# Robot_Psoc.net
KiCad netlist of a schematic drawn in EAGLE
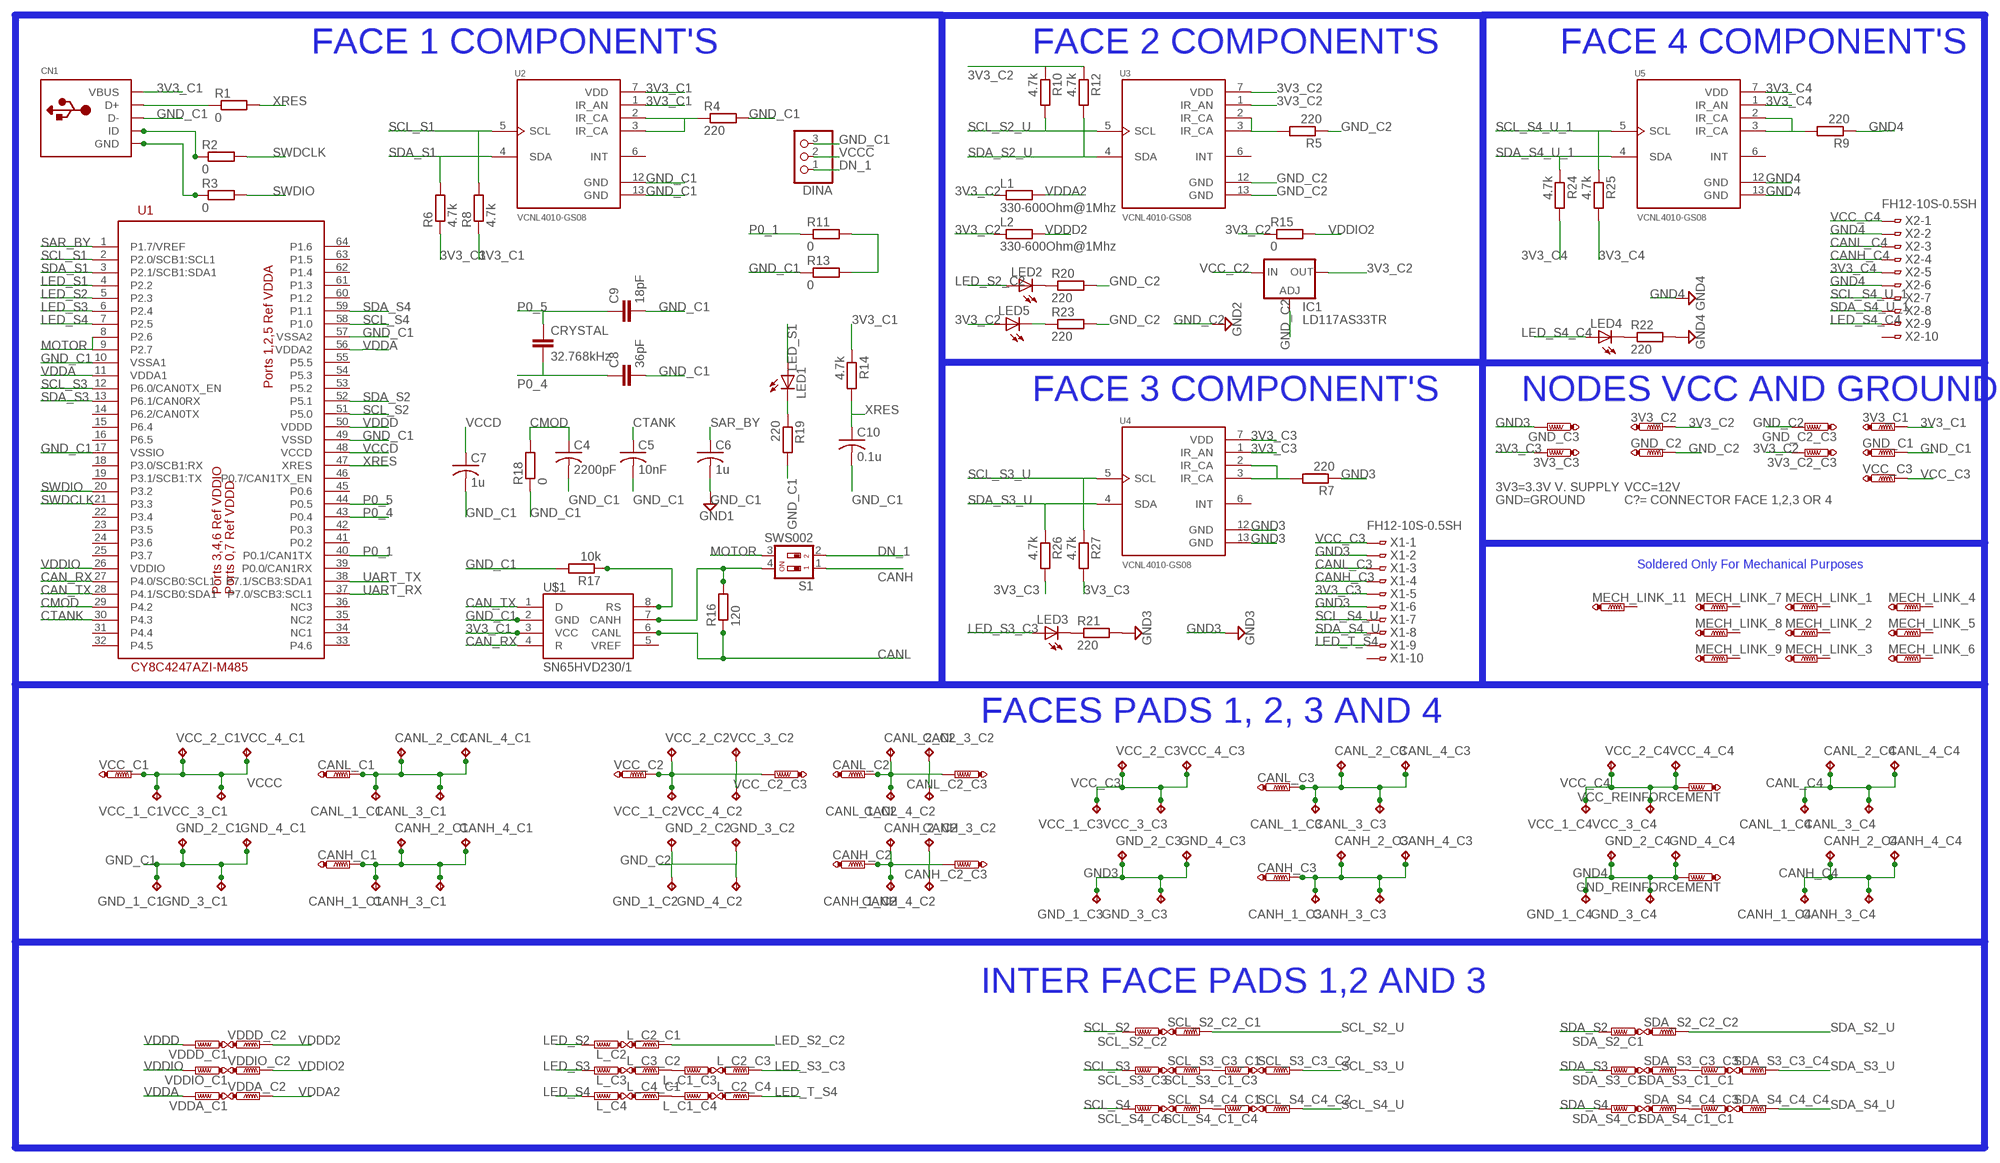
[diagram p0: schematic, sheet 1]

(export (version "E")
  (design (tool "Eeschema 10.0.6"))
  (components
    (comp (ref "3V3_C1")
      (value "PTR1TP11R")
      (footprint "eagle-import:TP11R")
      (libsource (lib "eagle-import") (part "PTR1TP11R"))
    )
    (comp (ref "3V3_C2")
      (value "PTR1TP11R")
      (footprint "eagle-import:TP11R")
      (libsource (lib "eagle-import") (part "PTR1TP11R"))
    )
    (comp (ref "3V3_C2_C3")
      (value "PTR1TP11R")
      (footprint "eagle-import:TP11R")
      (libsource (lib "eagle-import") (part "PTR1TP11R"))
    )
    (comp (ref "3V3_C3")
      (value "PTR1TP11R")
      (footprint "eagle-import:TP11R")
      (libsource (lib "eagle-import") (part "PTR1TP11R"))
    )
    (comp (ref "C4")
      (value "2200pF")
      (footprint "eagle-import:C0805")
      (libsource (lib "eagle-import") (part "C-USC0805"))
    )
    (comp (ref "C5")
      (value "10nF")
      (footprint "eagle-import:C0805")
      (libsource (lib "eagle-import") (part "C-USC0805"))
    )
    (comp (ref "C6")
      (value "1u")
      (footprint "eagle-import:C0805")
      (libsource (lib "eagle-import") (part "C-USC0805"))
    )
    (comp (ref "C7")
      (value "1u")
      (footprint "eagle-import:C0805")
      (libsource (lib "eagle-import") (part "C-USC0805"))
    )
    (comp (ref "C8")
      (value "36pF")
      (footprint "eagle-import:C0805")
      (libsource (lib "eagle-import") (part "C-EUC0805"))
    )
    (comp (ref "C9")
      (value "18pF")
      (footprint "eagle-import:C0805")
      (libsource (lib "eagle-import") (part "C-EUC0805"))
    )
    (comp (ref "C10")
      (value "0.1u")
      (footprint "eagle-import:C0805")
      (libsource (lib "eagle-import") (part "C-USC0805"))
    )
    (comp (ref "CANH_1_C1")
      (value "TPB2,54")
      (footprint "eagle-import:B2,54")
      (libsource (lib "eagle-import") (part "TPB2,54"))
    )
    (comp (ref "CANH_1_C2")
      (value "TPB2,54")
      (footprint "eagle-import:B2,54")
      (libsource (lib "eagle-import") (part "TPB2,54"))
    )
    (comp (ref "CANH_1_C3")
      (value "TPB2,54")
      (footprint "eagle-import:B2,54")
      (libsource (lib "eagle-import") (part "TPB2,54"))
    )
    (comp (ref "CANH_1_C4")
      (value "TPB2,54")
      (footprint "eagle-import:B2,54")
      (libsource (lib "eagle-import") (part "TPB2,54"))
    )
    (comp (ref "CANH_2_C1")
      (value "TPB2,54")
      (footprint "eagle-import:B2,54")
      (libsource (lib "eagle-import") (part "TPB2,54"))
    )
    (comp (ref "CANH_2_C2")
      (value "TPB2,54")
      (footprint "eagle-import:B2,54")
      (libsource (lib "eagle-import") (part "TPB2,54"))
    )
    (comp (ref "CANH_2_C3")
      (value "TPB2,54")
      (footprint "eagle-import:B2,54")
      (libsource (lib "eagle-import") (part "TPB2,54"))
    )
    (comp (ref "CANH_2_C4")
      (value "TPB2,54")
      (footprint "eagle-import:B2,54")
      (libsource (lib "eagle-import") (part "TPB2,54"))
    )
    (comp (ref "CANH_3_C1")
      (value "TPB2,54")
      (footprint "eagle-import:B2,54")
      (libsource (lib "eagle-import") (part "TPB2,54"))
    )
    (comp (ref "CANH_3_C2")
      (value "TPB2,54")
      (footprint "eagle-import:B2,54")
      (libsource (lib "eagle-import") (part "TPB2,54"))
    )
    (comp (ref "CANH_3_C3")
      (value "TPB2,54")
      (footprint "eagle-import:B2,54")
      (libsource (lib "eagle-import") (part "TPB2,54"))
    )
    (comp (ref "CANH_3_C4")
      (value "TPB2,54")
      (footprint "eagle-import:B2,54")
      (libsource (lib "eagle-import") (part "TPB2,54"))
    )
    (comp (ref "CANH_4_C1")
      (value "TPB2,54")
      (footprint "eagle-import:B2,54")
      (libsource (lib "eagle-import") (part "TPB2,54"))
    )
    (comp (ref "CANH_4_C2")
      (value "TPB2,54")
      (footprint "eagle-import:B2,54")
      (libsource (lib "eagle-import") (part "TPB2,54"))
    )
    (comp (ref "CANH_4_C3")
      (value "TPB2,54")
      (footprint "eagle-import:B2,54")
      (libsource (lib "eagle-import") (part "TPB2,54"))
    )
    (comp (ref "CANH_4_C4")
      (value "TPB2,54")
      (footprint "eagle-import:B2,54")
      (libsource (lib "eagle-import") (part "TPB2,54"))
    )
    (comp (ref "CANH_C1")
      (value "PTR1TP11R")
      (footprint "eagle-import:TP11R")
      (libsource (lib "eagle-import") (part "PTR1TP11R"))
    )
    (comp (ref "CANH_C2")
      (value "PTR1TP11R")
      (footprint "eagle-import:TP11R")
      (libsource (lib "eagle-import") (part "PTR1TP11R"))
    )
    (comp (ref "CANH_C2_C3")
      (value "PTR1TP11R")
      (footprint "eagle-import:TP11R")
      (libsource (lib "eagle-import") (part "PTR1TP11R"))
    )
    (comp (ref "CANH_C3")
      (value "PTR1TP11R")
      (footprint "eagle-import:TP11R")
      (libsource (lib "eagle-import") (part "PTR1TP11R"))
    )
    (comp (ref "CANL_1_C1")
      (value "TPB2,54")
      (footprint "eagle-import:B2,54")
      (libsource (lib "eagle-import") (part "TPB2,54"))
    )
    (comp (ref "CANL_1_C2")
      (value "TPB2,54")
      (footprint "eagle-import:B2,54")
      (libsource (lib "eagle-import") (part "TPB2,54"))
    )
    (comp (ref "CANL_1_C3")
      (value "TPB2,54")
      (footprint "eagle-import:B2,54")
      (libsource (lib "eagle-import") (part "TPB2,54"))
    )
    (comp (ref "CANL_1_C4")
      (value "TPB2,54")
      (footprint "eagle-import:B2,54")
      (libsource (lib "eagle-import") (part "TPB2,54"))
    )
    (comp (ref "CANL_2_C1")
      (value "TPB2,54")
      (footprint "eagle-import:B2,54")
      (libsource (lib "eagle-import") (part "TPB2,54"))
    )
    (comp (ref "CANL_2_C2")
      (value "TPB2,54")
      (footprint "eagle-import:B2,54")
      (libsource (lib "eagle-import") (part "TPB2,54"))
    )
    (comp (ref "CANL_2_C3")
      (value "TPB2,54")
      (footprint "eagle-import:B2,54")
      (libsource (lib "eagle-import") (part "TPB2,54"))
    )
    (comp (ref "CANL_2_C4")
      (value "TPB2,54")
      (footprint "eagle-import:B2,54")
      (libsource (lib "eagle-import") (part "TPB2,54"))
    )
    (comp (ref "CANL_3_C1")
      (value "TPB2,54")
      (footprint "eagle-import:B2,54")
      (libsource (lib "eagle-import") (part "TPB2,54"))
    )
    (comp (ref "CANL_3_C2")
      (value "TPB2,54")
      (footprint "eagle-import:B2,54")
      (libsource (lib "eagle-import") (part "TPB2,54"))
    )
    (comp (ref "CANL_3_C3")
      (value "TPB2,54")
      (footprint "eagle-import:B2,54")
      (libsource (lib "eagle-import") (part "TPB2,54"))
    )
    (comp (ref "CANL_3_C4")
      (value "TPB2,54")
      (footprint "eagle-import:B2,54")
      (libsource (lib "eagle-import") (part "TPB2,54"))
    )
    (comp (ref "CANL_4_C1")
      (value "TPB2,54")
      (footprint "eagle-import:B2,54")
      (libsource (lib "eagle-import") (part "TPB2,54"))
    )
    (comp (ref "CANL_4_C2")
      (value "TPB2,54")
      (footprint "eagle-import:B2,54")
      (libsource (lib "eagle-import") (part "TPB2,54"))
    )
    (comp (ref "CANL_4_C3")
      (value "TPB2,54")
      (footprint "eagle-import:B2,54")
      (libsource (lib "eagle-import") (part "TPB2,54"))
    )
    (comp (ref "CANL_4_C4")
      (value "TPB2,54")
      (footprint "eagle-import:B2,54")
      (libsource (lib "eagle-import") (part "TPB2,54"))
    )
    (comp (ref "CANL_C1")
      (value "PTR1TP11R")
      (footprint "eagle-import:TP11R")
      (libsource (lib "eagle-import") (part "PTR1TP11R"))
    )
    (comp (ref "CANL_C2")
      (value "PTR1TP11R")
      (footprint "eagle-import:TP11R")
      (libsource (lib "eagle-import") (part "PTR1TP11R"))
    )
    (comp (ref "CANL_C2_C3")
      (value "PTR1TP11R")
      (footprint "eagle-import:TP11R")
      (libsource (lib "eagle-import") (part "PTR1TP11R"))
    )
    (comp (ref "CANL_C3")
      (value "PTR1TP11R")
      (footprint "eagle-import:TP11R")
      (libsource (lib "eagle-import") (part "PTR1TP11R"))
    )
    (comp (ref "CN1")
      (value "USBMINIB")
      (footprint "eagle-import:USB-MINIB")
      (libsource (lib "eagle-import") (part "USBMINIB"))
    )
    (comp (ref "CRYSTAL")
      (value "32.768kHz")
      (footprint "eagle-import:C0603")
      (libsource (lib "eagle-import") (part "C-EUC0603"))
    )
    (comp (ref "DINA")
      (value "PINHD-1X3")
      (footprint "eagle-import:1X03")
      (libsource (lib "eagle-import") (part "PINHD-1X3"))
    )
    (comp (ref "GND_1_C1")
      (value "TPB2,54")
      (footprint "eagle-import:B2,54")
      (libsource (lib "eagle-import") (part "TPB2,54"))
    )
    (comp (ref "GND_1_C2")
      (value "TPB2,54")
      (footprint "eagle-import:B2,54")
      (libsource (lib "eagle-import") (part "TPB2,54"))
    )
    (comp (ref "GND_1_C3")
      (value "TPB2,54")
      (footprint "eagle-import:B2,54")
      (libsource (lib "eagle-import") (part "TPB2,54"))
    )
    (comp (ref "GND_1_C4")
      (value "TPB2,54")
      (footprint "eagle-import:B2,54")
      (libsource (lib "eagle-import") (part "TPB2,54"))
    )
    (comp (ref "GND_2_C1")
      (value "TPB2,54")
      (footprint "eagle-import:B2,54")
      (libsource (lib "eagle-import") (part "TPB2,54"))
    )
    (comp (ref "GND_2_C2")
      (value "TPB2,54")
      (footprint "eagle-import:B2,54")
      (libsource (lib "eagle-import") (part "TPB2,54"))
    )
    (comp (ref "GND_2_C3")
      (value "TPB2,54")
      (footprint "eagle-import:B2,54")
      (libsource (lib "eagle-import") (part "TPB2,54"))
    )
    (comp (ref "GND_2_C4")
      (value "TPB2,54")
      (footprint "eagle-import:B2,54")
      (libsource (lib "eagle-import") (part "TPB2,54"))
    )
    (comp (ref "GND_3_C1")
      (value "TPB2,54")
      (footprint "eagle-import:B2,54")
      (libsource (lib "eagle-import") (part "TPB2,54"))
    )
    (comp (ref "GND_3_C2")
      (value "TPB2,54")
      (footprint "eagle-import:B2,54")
      (libsource (lib "eagle-import") (part "TPB2,54"))
    )
    (comp (ref "GND_3_C3")
      (value "TPB2,54")
      (footprint "eagle-import:B2,54")
      (libsource (lib "eagle-import") (part "TPB2,54"))
    )
    (comp (ref "GND_3_C4")
      (value "TPB2,54")
      (footprint "eagle-import:B2,54")
      (libsource (lib "eagle-import") (part "TPB2,54"))
    )
    (comp (ref "GND_4_C1")
      (value "TPB2,54")
      (footprint "eagle-import:B2,54")
      (libsource (lib "eagle-import") (part "TPB2,54"))
    )
    (comp (ref "GND_4_C2")
      (value "TPB2,54")
      (footprint "eagle-import:B2,54")
      (libsource (lib "eagle-import") (part "TPB2,54"))
    )
    (comp (ref "GND_4_C3")
      (value "TPB2,54")
      (footprint "eagle-import:B2,54")
      (libsource (lib "eagle-import") (part "TPB2,54"))
    )
    (comp (ref "GND_4_C4")
      (value "TPB2,54")
      (footprint "eagle-import:B2,54")
      (libsource (lib "eagle-import") (part "TPB2,54"))
    )
    (comp (ref "GND_C1")
      (value "PTR1TP11R")
      (footprint "eagle-import:TP11R")
      (libsource (lib "eagle-import") (part "PTR1TP11R"))
    )
    (comp (ref "GND_C2")
      (value "PTR1TP11R")
      (footprint "eagle-import:TP11R")
      (libsource (lib "eagle-import") (part "PTR1TP11R"))
    )
    (comp (ref "GND_C2_C3")
      (value "PTR1TP11R")
      (footprint "eagle-import:TP11R")
      (libsource (lib "eagle-import") (part "PTR1TP11R"))
    )
    (comp (ref "GND_C3")
      (value "PTR1TP11R")
      (footprint "eagle-import:TP11R")
      (libsource (lib "eagle-import") (part "PTR1TP11R"))
    )
    (comp (ref "GND_REINFORCEMENT")
      (value "PTR1TP11R")
      (footprint "eagle-import:TP11R")
      (libsource (lib "eagle-import") (part "PTR1TP11R"))
    )
    (comp (ref "IC1")
      (value "LD117AS33TR")
      (footprint "eagle-import:SOT223")
      (libsource (lib "eagle-import") (part "LD117A?S33TR"))
    )
    (comp (ref "L1")
      (value "330-600Ohm@1Mhz")
      (footprint "eagle-import:R0805")
      (libsource (lib "eagle-import") (part "R-EU_R0805"))
    )
    (comp (ref "L2")
      (value "330-600Ohm@1Mhz")
      (footprint "eagle-import:R0805")
      (libsource (lib "eagle-import") (part "R-EU_R0805"))
    )
    (comp (ref "LED1")
      (value "LEDCHIPLED_0805")
      (footprint "eagle-import:CHIPLED_0805")
      (libsource (lib "eagle-import") (part "LEDCHIPLED_0805"))
    )
    (comp (ref "LED2")
      (value "LEDCHIPLED_0805")
      (footprint "eagle-import:CHIPLED_0805")
      (libsource (lib "eagle-import") (part "LEDCHIPLED_0805"))
    )
    (comp (ref "LED3")
      (value "LEDCHIPLED_0805")
      (footprint "eagle-import:CHIPLED_0805")
      (libsource (lib "eagle-import") (part "LEDCHIPLED_0805"))
    )
    (comp (ref "LED4")
      (value "LEDCHIPLED_0805")
      (footprint "eagle-import:CHIPLED_0805")
      (libsource (lib "eagle-import") (part "LEDCHIPLED_0805"))
    )
    (comp (ref "LED5")
      (value "LEDCHIPLED_0805")
      (footprint "eagle-import:CHIPLED_0805")
      (libsource (lib "eagle-import") (part "LEDCHIPLED_0805"))
    )
    (comp (ref "L_C1_C3")
      (value "PTR1TP11R")
      (footprint "eagle-import:TP11R")
      (libsource (lib "eagle-import") (part "PTR1TP11R"))
    )
    (comp (ref "L_C1_C4")
      (value "PTR1TP11R")
      (footprint "eagle-import:TP11R")
      (libsource (lib "eagle-import") (part "PTR1TP11R"))
    )
    (comp (ref "L_C2")
      (value "PTR1TP11R")
      (footprint "eagle-import:TP11R")
      (libsource (lib "eagle-import") (part "PTR1TP11R"))
    )
    (comp (ref "L_C2_C1")
      (value "PTR1TP11R")
      (footprint "eagle-import:TP11R")
      (libsource (lib "eagle-import") (part "PTR1TP11R"))
    )
    (comp (ref "L_C2_C3")
      (value "PTR1TP11R")
      (footprint "eagle-import:TP11R")
      (libsource (lib "eagle-import") (part "PTR1TP11R"))
    )
    (comp (ref "L_C2_C4")
      (value "PTR1TP11R")
      (footprint "eagle-import:TP11R")
      (libsource (lib "eagle-import") (part "PTR1TP11R"))
    )
    (comp (ref "L_C3")
      (value "PTR1TP11R")
      (footprint "eagle-import:TP11R")
      (libsource (lib "eagle-import") (part "PTR1TP11R"))
    )
    (comp (ref "L_C3_C2")
      (value "PTR1TP11R")
      (footprint "eagle-import:TP11R")
      (libsource (lib "eagle-import") (part "PTR1TP11R"))
    )
    (comp (ref "L_C4")
      (value "PTR1TP11R")
      (footprint "eagle-import:TP11R")
      (libsource (lib "eagle-import") (part "PTR1TP11R"))
    )
    (comp (ref "L_C4_C1")
      (value "PTR1TP11R")
      (footprint "eagle-import:TP11R")
      (libsource (lib "eagle-import") (part "PTR1TP11R"))
    )
    (comp (ref "MECH_LINK_1")
      (value "PTR1TP11R")
      (footprint "eagle-import:TP11R")
      (libsource (lib "eagle-import") (part "PTR1TP11R"))
    )
    (comp (ref "MECH_LINK_2")
      (value "PTR1TP11R")
      (footprint "eagle-import:TP11R")
      (libsource (lib "eagle-import") (part "PTR1TP11R"))
    )
    (comp (ref "MECH_LINK_3")
      (value "PTR1TP11R")
      (footprint "eagle-import:TP11R")
      (libsource (lib "eagle-import") (part "PTR1TP11R"))
    )
    (comp (ref "MECH_LINK_4")
      (value "PTR1TP11R")
      (footprint "eagle-import:TP11R")
      (libsource (lib "eagle-import") (part "PTR1TP11R"))
    )
    (comp (ref "MECH_LINK_5")
      (value "PTR1TP11R")
      (footprint "eagle-import:TP11R")
      (libsource (lib "eagle-import") (part "PTR1TP11R"))
    )
    (comp (ref "MECH_LINK_6")
      (value "PTR1TP11R")
      (footprint "eagle-import:TP11R")
      (libsource (lib "eagle-import") (part "PTR1TP11R"))
    )
    (comp (ref "MECH_LINK_7")
      (value "PTR1TP11R")
      (footprint "eagle-import:TP11R")
      (libsource (lib "eagle-import") (part "PTR1TP11R"))
    )
    (comp (ref "MECH_LINK_8")
      (value "PTR1TP11R")
      (footprint "eagle-import:TP11R")
      (libsource (lib "eagle-import") (part "PTR1TP11R"))
    )
    (comp (ref "MECH_LINK_9")
      (value "PTR1TP11R")
      (footprint "eagle-import:TP11R")
      (libsource (lib "eagle-import") (part "PTR1TP11R"))
    )
    (comp (ref "MECH_LINK_11")
      (value "PTR1TP11R")
      (footprint "eagle-import:TP11R")
      (libsource (lib "eagle-import") (part "PTR1TP11R"))
    )
    (comp (ref "R1")
      (value "0")
      (footprint "eagle-import:R0805")
      (libsource (lib "eagle-import") (part "R-EU_R0805"))
    )
    (comp (ref "R2")
      (value "0")
      (footprint "eagle-import:R0805")
      (libsource (lib "eagle-import") (part "R-EU_R0805"))
    )
    (comp (ref "R3")
      (value "0")
      (footprint "eagle-import:R0805")
      (libsource (lib "eagle-import") (part "R-EU_R0805"))
    )
    (comp (ref "R4")
      (value "220")
      (footprint "eagle-import:R0805")
      (libsource (lib "eagle-import") (part "R-EU_R0805"))
    )
    (comp (ref "R5")
      (value "220")
      (footprint "eagle-import:R0805")
      (libsource (lib "eagle-import") (part "R-EU_R0805"))
    )
    (comp (ref "R6")
      (value "4.7k")
      (footprint "eagle-import:R0805")
      (libsource (lib "eagle-import") (part "R-EU_R0805"))
    )
    (comp (ref "R7")
      (value "220")
      (footprint "eagle-import:R0805")
      (libsource (lib "eagle-import") (part "R-EU_R0805"))
    )
    (comp (ref "R8")
      (value "4.7k")
      (footprint "eagle-import:R0805")
      (libsource (lib "eagle-import") (part "R-EU_R0805"))
    )
    (comp (ref "R9")
      (value "220")
      (footprint "eagle-import:R0805")
      (libsource (lib "eagle-import") (part "R-EU_R0805"))
    )
    (comp (ref "R10")
      (value "4.7k")
      (footprint "eagle-import:R0805")
      (libsource (lib "eagle-import") (part "R-EU_R0805"))
    )
    (comp (ref "R11")
      (value "0")
      (footprint "eagle-import:R0805")
      (libsource (lib "eagle-import") (part "R-EU_R0805"))
    )
    (comp (ref "R12")
      (value "4.7k")
      (footprint "eagle-import:R0805")
      (libsource (lib "eagle-import") (part "R-EU_R0805"))
    )
    (comp (ref "R13")
      (value "0")
      (footprint "eagle-import:R0805")
      (libsource (lib "eagle-import") (part "R-EU_R0805"))
    )
    (comp (ref "R14")
      (value "4.7k")
      (footprint "eagle-import:R0805")
      (libsource (lib "eagle-import") (part "R-EU_R0805"))
    )
    (comp (ref "R15")
      (value "0")
      (footprint "eagle-import:R0805")
      (libsource (lib "eagle-import") (part "R-EU_R0805"))
    )
    (comp (ref "R16")
      (value "120")
      (footprint "eagle-import:R0805")
      (libsource (lib "eagle-import") (part "R-EU_R0805"))
    )
    (comp (ref "R17")
      (value "10k")
      (footprint "eagle-import:R0805")
      (libsource (lib "eagle-import") (part "R-EU_R0805"))
    )
    (comp (ref "R18")
      (value "0")
      (footprint "eagle-import:R0805")
      (libsource (lib "eagle-import") (part "R-EU_R0805"))
    )
    (comp (ref "R19")
      (value "220")
      (footprint "eagle-import:R0805")
      (libsource (lib "eagle-import") (part "R-EU_R0805"))
    )
    (comp (ref "R20")
      (value "220")
      (footprint "eagle-import:R0805")
      (libsource (lib "eagle-import") (part "R-EU_R0805"))
    )
    (comp (ref "R21")
      (value "220")
      (footprint "eagle-import:R0805")
      (libsource (lib "eagle-import") (part "R-EU_R0805"))
    )
    (comp (ref "R22")
      (value "220")
      (footprint "eagle-import:R0805")
      (libsource (lib "eagle-import") (part "R-EU_R0805"))
    )
    (comp (ref "R23")
      (value "220")
      (footprint "eagle-import:R0805")
      (libsource (lib "eagle-import") (part "R-EU_R0805"))
    )
    (comp (ref "R24")
      (value "4.7k")
      (footprint "eagle-import:R0805")
      (libsource (lib "eagle-import") (part "R-EU_R0805"))
    )
    (comp (ref "R25")
      (value "4.7k")
      (footprint "eagle-import:R0805")
      (libsource (lib "eagle-import") (part "R-EU_R0805"))
    )
    (comp (ref "R26")
      (value "4.7k")
      (footprint "eagle-import:R0805")
      (libsource (lib "eagle-import") (part "R-EU_R0805"))
    )
    (comp (ref "R27")
      (value "4.7k")
      (footprint "eagle-import:R0805")
      (libsource (lib "eagle-import") (part "R-EU_R0805"))
    )
    (comp (ref "S1")
      (value "SWS002")
      (footprint "eagle-import:SMS-002")
      (libsource (lib "eagle-import") (part "SWS002"))
    )
    (comp (ref "SCL_S2_C2")
      (value "PTR1TP11R")
      (footprint "eagle-import:TP11R")
      (libsource (lib "eagle-import") (part "PTR1TP11R"))
    )
    (comp (ref "SCL_S2_C2_C1")
      (value "PTR1TP11R")
      (footprint "eagle-import:TP11R")
      (libsource (lib "eagle-import") (part "PTR1TP11R"))
    )
    (comp (ref "SCL_S3_C1_C3")
      (value "PTR1TP11R")
      (footprint "eagle-import:TP11R")
      (libsource (lib "eagle-import") (part "PTR1TP11R"))
    )
    (comp (ref "SCL_S3_C3")
      (value "PTR1TP11R")
      (footprint "eagle-import:TP11R")
      (libsource (lib "eagle-import") (part "PTR1TP11R"))
    )
    (comp (ref "SCL_S3_C3_C1")
      (value "PTR1TP11R")
      (footprint "eagle-import:TP11R")
      (libsource (lib "eagle-import") (part "PTR1TP11R"))
    )
    (comp (ref "SCL_S3_C3_C2")
      (value "PTR1TP11R")
      (footprint "eagle-import:TP11R")
      (libsource (lib "eagle-import") (part "PTR1TP11R"))
    )
    (comp (ref "SCL_S4_C1_C4")
      (value "PTR1TP11R")
      (footprint "eagle-import:TP11R")
      (libsource (lib "eagle-import") (part "PTR1TP11R"))
    )
    (comp (ref "SCL_S4_C4")
      (value "PTR1TP11R")
      (footprint "eagle-import:TP11R")
      (libsource (lib "eagle-import") (part "PTR1TP11R"))
    )
    (comp (ref "SCL_S4_C4_C1")
      (value "PTR1TP11R")
      (footprint "eagle-import:TP11R")
      (libsource (lib "eagle-import") (part "PTR1TP11R"))
    )
    (comp (ref "SCL_S4_C4_C2")
      (value "PTR1TP11R")
      (footprint "eagle-import:TP11R")
      (libsource (lib "eagle-import") (part "PTR1TP11R"))
    )
    (comp (ref "SDA_S2_C1")
      (value "PTR1TP11R")
      (footprint "eagle-import:TP11R")
      (libsource (lib "eagle-import") (part "PTR1TP11R"))
    )
    (comp (ref "SDA_S2_C2_C2")
      (value "PTR1TP11R")
      (footprint "eagle-import:TP11R")
      (libsource (lib "eagle-import") (part "PTR1TP11R"))
    )
    (comp (ref "SDA_S3_C1")
      (value "PTR1TP11R")
      (footprint "eagle-import:TP11R")
      (libsource (lib "eagle-import") (part "PTR1TP11R"))
    )
    (comp (ref "SDA_S3_C1_C1")
      (value "PTR1TP11R")
      (footprint "eagle-import:TP11R")
      (libsource (lib "eagle-import") (part "PTR1TP11R"))
    )
    (comp (ref "SDA_S3_C3_C3")
      (value "PTR1TP11R")
      (footprint "eagle-import:TP11R")
      (libsource (lib "eagle-import") (part "PTR1TP11R"))
    )
    (comp (ref "SDA_S3_C3_C4")
      (value "PTR1TP11R")
      (footprint "eagle-import:TP11R")
      (libsource (lib "eagle-import") (part "PTR1TP11R"))
    )
    (comp (ref "SDA_S4_C1")
      (value "PTR1TP11R")
      (footprint "eagle-import:TP11R")
      (libsource (lib "eagle-import") (part "PTR1TP11R"))
    )
    (comp (ref "SDA_S4_C1_C1")
      (value "PTR1TP11R")
      (footprint "eagle-import:TP11R")
      (libsource (lib "eagle-import") (part "PTR1TP11R"))
    )
    (comp (ref "SDA_S4_C4_C3")
      (value "PTR1TP11R")
      (footprint "eagle-import:TP11R")
      (libsource (lib "eagle-import") (part "PTR1TP11R"))
    )
    (comp (ref "SDA_S4_C4_C4")
      (value "PTR1TP11R")
      (footprint "eagle-import:TP11R")
      (libsource (lib "eagle-import") (part "PTR1TP11R"))
    )
    (comp (ref "U$1")
      (value "SN65HVD230/1")
      (footprint "eagle-import:SO8")
      (libsource (lib "eagle-import") (part "SN65HVD230/1"))
    )
    (comp (ref "U1")
      (value "CY8C4247AZI-M485")
      (footprint "eagle-import:TQFP64-10X10")
      (libsource (lib "eagle-import") (part "CY8C4247AZI-M485"))
    )
    (comp (ref "U2")
      (value "VCNL4010-GS08")
      (footprint "eagle-import:XDCR_VCNL4010-GS08")
      (libsource (lib "eagle-import") (part "VCNL4010-GS08"))
    )
    (comp (ref "U3")
      (value "VCNL4010-GS08")
      (footprint "eagle-import:XDCR_VCNL4010-GS08")
      (libsource (lib "eagle-import") (part "VCNL4010-GS08"))
    )
    (comp (ref "U4")
      (value "VCNL4010-GS08")
      (footprint "eagle-import:XDCR_VCNL4010-GS08")
      (libsource (lib "eagle-import") (part "VCNL4010-GS08"))
    )
    (comp (ref "U5")
      (value "VCNL4010-GS08")
      (footprint "eagle-import:XDCR_VCNL4010-GS08")
      (libsource (lib "eagle-import") (part "VCNL4010-GS08"))
    )
    (comp (ref "VCC_1_C1")
      (value "TPB2,54")
      (footprint "eagle-import:B2,54")
      (libsource (lib "eagle-import") (part "TPB2,54"))
    )
    (comp (ref "VCC_1_C2")
      (value "TPB2,54")
      (footprint "eagle-import:B2,54")
      (libsource (lib "eagle-import") (part "TPB2,54"))
    )
    (comp (ref "VCC_1_C3")
      (value "TPB2,54")
      (footprint "eagle-import:B2,54")
      (libsource (lib "eagle-import") (part "TPB2,54"))
    )
    (comp (ref "VCC_1_C4")
      (value "TPB2,54")
      (footprint "eagle-import:B2,54")
      (libsource (lib "eagle-import") (part "TPB2,54"))
    )
    (comp (ref "VCC_2_C1")
      (value "TPB2,54")
      (footprint "eagle-import:B2,54")
      (libsource (lib "eagle-import") (part "TPB2,54"))
    )
    (comp (ref "VCC_2_C2")
      (value "TPB2,54")
      (footprint "eagle-import:B2,54")
      (libsource (lib "eagle-import") (part "TPB2,54"))
    )
    (comp (ref "VCC_2_C3")
      (value "TPB2,54")
      (footprint "eagle-import:B2,54")
      (libsource (lib "eagle-import") (part "TPB2,54"))
    )
    (comp (ref "VCC_2_C4")
      (value "TPB2,54")
      (footprint "eagle-import:B2,54")
      (libsource (lib "eagle-import") (part "TPB2,54"))
    )
    (comp (ref "VCC_3_C1")
      (value "TPB2,54")
      (footprint "eagle-import:B2,54")
      (libsource (lib "eagle-import") (part "TPB2,54"))
    )
    (comp (ref "VCC_3_C2")
      (value "TPB2,54")
      (footprint "eagle-import:B2,54")
      (libsource (lib "eagle-import") (part "TPB2,54"))
    )
    (comp (ref "VCC_3_C3")
      (value "TPB2,54")
      (footprint "eagle-import:B2,54")
      (libsource (lib "eagle-import") (part "TPB2,54"))
    )
    (comp (ref "VCC_3_C4")
      (value "TPB2,54")
      (footprint "eagle-import:B2,54")
      (libsource (lib "eagle-import") (part "TPB2,54"))
    )
    (comp (ref "VCC_4_C1")
      (value "TPB2,54")
      (footprint "eagle-import:B2,54")
      (libsource (lib "eagle-import") (part "TPB2,54"))
    )
    (comp (ref "VCC_4_C2")
      (value "TPB2,54")
      (footprint "eagle-import:B2,54")
      (libsource (lib "eagle-import") (part "TPB2,54"))
    )
    (comp (ref "VCC_4_C3")
      (value "TPB2,54")
      (footprint "eagle-import:B2,54")
      (libsource (lib "eagle-import") (part "TPB2,54"))
    )
    (comp (ref "VCC_4_C4")
      (value "TPB2,54")
      (footprint "eagle-import:B2,54")
      (libsource (lib "eagle-import") (part "TPB2,54"))
    )
    (comp (ref "VCC_C1")
      (value "PTR1TP11R")
      (footprint "eagle-import:TP11R")
      (libsource (lib "eagle-import") (part "PTR1TP11R"))
    )
    (comp (ref "VCC_C2")
      (value "PTR1TP11R")
      (footprint "eagle-import:TP11R")
      (libsource (lib "eagle-import") (part "PTR1TP11R"))
    )
    (comp (ref "VCC_C2_C3")
      (value "PTR1TP11R")
      (footprint "eagle-import:TP11R")
      (libsource (lib "eagle-import") (part "PTR1TP11R"))
    )
    (comp (ref "VCC_C3")
      (value "PTR1TP11R")
      (footprint "eagle-import:TP11R")
      (libsource (lib "eagle-import") (part "PTR1TP11R"))
    )
    (comp (ref "VCC_REINFORCEMENT")
      (value "PTR1TP11R")
      (footprint "eagle-import:TP11R")
      (libsource (lib "eagle-import") (part "PTR1TP11R"))
    )
    (comp (ref "VDDA_C1")
      (value "PTR1TP11R")
      (footprint "eagle-import:TP11R")
      (libsource (lib "eagle-import") (part "PTR1TP11R"))
    )
    (comp (ref "VDDA_C2")
      (value "PTR1TP11R")
      (footprint "eagle-import:TP11R")
      (libsource (lib "eagle-import") (part "PTR1TP11R"))
    )
    (comp (ref "VDDD_C1")
      (value "PTR1TP11R")
      (footprint "eagle-import:TP11R")
      (libsource (lib "eagle-import") (part "PTR1TP11R"))
    )
    (comp (ref "VDDD_C2")
      (value "PTR1TP11R")
      (footprint "eagle-import:TP11R")
      (libsource (lib "eagle-import") (part "PTR1TP11R"))
    )
    (comp (ref "VDDIO_C1")
      (value "PTR1TP11R")
      (footprint "eagle-import:TP11R")
      (libsource (lib "eagle-import") (part "PTR1TP11R"))
    )
    (comp (ref "VDDIO_C2")
      (value "PTR1TP11R")
      (footprint "eagle-import:TP11R")
      (libsource (lib "eagle-import") (part "PTR1TP11R"))
    )
    (comp (ref "X1")
      (value "FH12-10S-0.5SH")
      (footprint "eagle-import:FH12-10S-0.5SH")
      (fields (field (name "MPN") "FH12-10S-0.5SH(55)"))
      (libsource (lib "eagle-import") (part "FH12-10S-0.5SH"))
    )
    (comp (ref "X2")
      (value "FH12-10S-0.5SH")
      (footprint "eagle-import:FH12-10S-0.5SH")
      (fields (field (name "MPN") "FH12-10S-0.5SH(55)"))
      (libsource (lib "eagle-import") (part "FH12-10S-0.5SH"))
    )
  )
  (nets
    (net (code "1") (name "/3V3_C1") (class "Default")
      (node (ref "3V3_C1") (pin "TP") (pinfunction "TP_TP") (pintype "input"))
      (node (ref "CN1") (pin "VBUS") (pinfunction "VBUS_VBUS") (pintype "power_in"))
      (node (ref "R14") (pin "1") (pinfunction "1_1") (pintype "passive"))
      (node (ref "R6") (pin "1") (pinfunction "1_1") (pintype "passive"))
      (node (ref "R8") (pin "1") (pinfunction "1_1") (pintype "passive"))
      (node (ref "U$1") (pin "3") (pinfunction "VCC_3") (pintype "power_in"))
      (node (ref "U2") (pin "1") (pinfunction "IR_AN_1") (pintype "power_in"))
      (node (ref "U2") (pin "7") (pinfunction "VDD_7") (pintype "power_in"))
    )
    (net (code "2") (name "/3V3_C2") (class "Default")
      (node (ref "3V3_C2") (pin "TP") (pinfunction "TP_TP") (pintype "input"))
      (node (ref "3V3_C2_C3") (pin "TP") (pinfunction "TP_TP") (pintype "input"))
      (node (ref "IC1") (pin "4") (pinfunction "OUT_4") (pintype "passive"))
      (node (ref "L1") (pin "1") (pinfunction "1_1") (pintype "passive"))
      (node (ref "L2") (pin "1") (pinfunction "1_1") (pintype "passive"))
      (node (ref "LED5") (pin "A") (pinfunction "A_A") (pintype "passive"))
      (node (ref "R10") (pin "1") (pinfunction "1_1") (pintype "passive"))
      (node (ref "R12") (pin "1") (pinfunction "1_1") (pintype "passive"))
      (node (ref "R15") (pin "1") (pinfunction "1_1") (pintype "passive"))
      (node (ref "U3") (pin "1") (pinfunction "IR_AN_1") (pintype "power_in"))
      (node (ref "U3") (pin "7") (pinfunction "VDD_7") (pintype "power_in"))
    )
    (net (code "3") (name "/3V3_C3") (class "Default")
      (node (ref "3V3_C3") (pin "TP") (pinfunction "TP_TP") (pintype "input"))
      (node (ref "R26") (pin "2") (pinfunction "2_2") (pintype "passive"))
      (node (ref "R27") (pin "2") (pinfunction "2_2") (pintype "passive"))
      (node (ref "U4") (pin "1") (pinfunction "IR_AN_1") (pintype "power_in"))
      (node (ref "U4") (pin "7") (pinfunction "VDD_7") (pintype "power_in"))
      (node (ref "X1") (pin "5") (pinfunction "1_5") (pintype "passive"))
    )
    (net (code "4") (name "/3V3_C4") (class "Default")
      (node (ref "R24") (pin "2") (pinfunction "2_2") (pintype "passive"))
      (node (ref "R25") (pin "2") (pinfunction "2_2") (pintype "passive"))
      (node (ref "U5") (pin "1") (pinfunction "IR_AN_1") (pintype "power_in"))
      (node (ref "U5") (pin "7") (pinfunction "VDD_7") (pintype "power_in"))
      (node (ref "X2") (pin "5") (pinfunction "1_5") (pintype "passive"))
    )
    (net (code "5") (name "/CANH") (class "Default")
      (node (ref "CANH_1_C1") (pin "TP") (pinfunction "TP_TP") (pintype "input"))
      (node (ref "CANH_2_C1") (pin "TP") (pinfunction "TP_TP") (pintype "input"))
      (node (ref "CANH_3_C1") (pin "TP") (pinfunction "TP_TP") (pintype "input"))
      (node (ref "CANH_4_C1") (pin "TP") (pinfunction "TP_TP") (pintype "input"))
      (node (ref "CANH_C1") (pin "TP") (pinfunction "TP_TP") (pintype "input"))
      (node (ref "S1") (pin "1") (pinfunction "1_1") (pintype "passive"))
    )
    (net (code "6") (name "/CANH_C3") (class "Default")
      (node (ref "CANH_1_C3") (pin "TP") (pinfunction "TP_TP") (pintype "input"))
      (node (ref "CANH_2_C3") (pin "TP") (pinfunction "TP_TP") (pintype "input"))
      (node (ref "CANH_3_C3") (pin "TP") (pinfunction "TP_TP") (pintype "input"))
      (node (ref "CANH_4_C3") (pin "TP") (pinfunction "TP_TP") (pintype "input"))
      (node (ref "CANH_C3") (pin "TP") (pinfunction "TP_TP") (pintype "input"))
      (node (ref "X1") (pin "4") (pinfunction "1_4") (pintype "passive"))
    )
    (net (code "7") (name "/CANH_C4") (class "Default")
      (node (ref "CANH_1_C4") (pin "TP") (pinfunction "TP_TP") (pintype "input"))
      (node (ref "CANH_2_C4") (pin "TP") (pinfunction "TP_TP") (pintype "input"))
      (node (ref "CANH_3_C4") (pin "TP") (pinfunction "TP_TP") (pintype "input"))
      (node (ref "CANH_4_C4") (pin "TP") (pinfunction "TP_TP") (pintype "input"))
      (node (ref "X2") (pin "4") (pinfunction "1_4") (pintype "passive"))
    )
    (net (code "8") (name "/CANL") (class "Default")
      (node (ref "CANL_1_C1") (pin "TP") (pinfunction "TP_TP") (pintype "input"))
      (node (ref "CANL_2_C1") (pin "TP") (pinfunction "TP_TP") (pintype "input"))
      (node (ref "CANL_3_C1") (pin "TP") (pinfunction "TP_TP") (pintype "input"))
      (node (ref "CANL_4_C1") (pin "TP") (pinfunction "TP_TP") (pintype "input"))
      (node (ref "CANL_C1") (pin "TP") (pinfunction "TP_TP") (pintype "input"))
      (node (ref "R16") (pin "1") (pinfunction "1_1") (pintype "passive"))
      (node (ref "U$1") (pin "6") (pinfunction "CANL_6") (pintype "bidirectional"))
    )
    (net (code "9") (name "/CANL_C3") (class "Default")
      (node (ref "CANL_1_C3") (pin "TP") (pinfunction "TP_TP") (pintype "input"))
      (node (ref "CANL_2_C3") (pin "TP") (pinfunction "TP_TP") (pintype "input"))
      (node (ref "CANL_3_C3") (pin "TP") (pinfunction "TP_TP") (pintype "input"))
      (node (ref "CANL_4_C3") (pin "TP") (pinfunction "TP_TP") (pintype "input"))
      (node (ref "CANL_C3") (pin "TP") (pinfunction "TP_TP") (pintype "input"))
      (node (ref "X1") (pin "3") (pinfunction "1_3") (pintype "passive"))
    )
    (net (code "10") (name "/CANL_C4") (class "Default")
      (node (ref "CANL_1_C4") (pin "TP") (pinfunction "TP_TP") (pintype "input"))
      (node (ref "CANL_2_C4") (pin "TP") (pinfunction "TP_TP") (pintype "input"))
      (node (ref "CANL_3_C4") (pin "TP") (pinfunction "TP_TP") (pintype "input"))
      (node (ref "CANL_4_C4") (pin "TP") (pinfunction "TP_TP") (pintype "input"))
      (node (ref "X2") (pin "3") (pinfunction "1_3") (pintype "passive"))
    )
    (net (code "11") (name "/CAN_RX") (class "Default")
      (node (ref "U$1") (pin "4") (pinfunction "R_4") (pintype "bidirectional"))
      (node (ref "U1") (pin "27") (pinfunction "P4.0/SCB0:SCL1_27") (pintype "bidirectional"))
    )
    (net (code "12") (name "/CAN_TX") (class "Default")
      (node (ref "U$1") (pin "1") (pinfunction "D_1") (pintype "bidirectional"))
      (node (ref "U1") (pin "28") (pinfunction "P4.1/SCB0:SDA1_28") (pintype "bidirectional"))
    )
    (net (code "13") (name "/CMOD") (class "Default")
      (node (ref "C4") (pin "1") (pinfunction "1_1") (pintype "passive"))
      (node (ref "R18") (pin "2") (pinfunction "2_2") (pintype "passive"))
      (node (ref "U1") (pin "29") (pinfunction "P4.2_29") (pintype "bidirectional"))
    )
    (net (code "14") (name "/CTANK") (class "Default")
      (node (ref "C5") (pin "1") (pinfunction "1_1") (pintype "passive"))
      (node (ref "U1") (pin "30") (pinfunction "P4.3_30") (pintype "bidirectional"))
    )
    (net (code "15") (name "/DN_1") (class "Default")
      (node (ref "DINA") (pin "1") (pinfunction "1_1") (pintype "passive"))
      (node (ref "S1") (pin "2") (pinfunction "2_2") (pintype "passive"))
    )
    (net (code "16") (name "/LED_S1") (class "Default")
      (node (ref "LED1") (pin "A") (pinfunction "A_A") (pintype "passive"))
      (node (ref "U1") (pin "4") (pinfunction "P2.2_4") (pintype "bidirectional"))
    )
    (net (code "17") (name "/LED_S2") (class "Default")
      (node (ref "L_C2") (pin "TP") (pinfunction "TP_TP") (pintype "input"))
      (node (ref "U1") (pin "5") (pinfunction "P2.3_5") (pintype "bidirectional"))
    )
    (net (code "18") (name "/LED_S2_C2") (class "Default")
      (node (ref "LED2") (pin "A") (pinfunction "A_A") (pintype "passive"))
      (node (ref "L_C2_C1") (pin "TP") (pinfunction "TP_TP") (pintype "input"))
    )
    (net (code "19") (name "/LED_S3") (class "Default")
      (node (ref "L_C3") (pin "TP") (pinfunction "TP_TP") (pintype "input"))
      (node (ref "U1") (pin "6") (pinfunction "P2.4_6") (pintype "bidirectional"))
    )
    (net (code "20") (name "/LED_S3_C3") (class "Default")
      (node (ref "LED3") (pin "A") (pinfunction "A_A") (pintype "passive"))
      (node (ref "L_C2_C3") (pin "TP") (pinfunction "TP_TP") (pintype "input"))
    )
    (net (code "21") (name "/LED_S4") (class "Default")
      (node (ref "L_C4") (pin "TP") (pinfunction "TP_TP") (pintype "input"))
      (node (ref "U1") (pin "7") (pinfunction "P2.5_7") (pintype "bidirectional"))
    )
    (net (code "22") (name "/LED_S4_C4") (class "Default")
      (node (ref "LED4") (pin "A") (pinfunction "A_A") (pintype "passive"))
      (node (ref "X2") (pin "9") (pinfunction "1_9") (pintype "passive"))
    )
    (net (code "23") (name "/LED_T_S4") (class "Default")
      (node (ref "L_C2_C4") (pin "TP") (pinfunction "TP_TP") (pintype "input"))
      (node (ref "X1") (pin "9") (pinfunction "1_9") (pintype "passive"))
    )
    (net (code "24") (name "/MOTOR") (class "Default")
      (node (ref "S1") (pin "3") (pinfunction "3_3") (pintype "passive"))
      (node (ref "U1") (pin "8") (pinfunction "P2.6_8") (pintype "bidirectional"))
      (node (ref "U1") (pin "9") (pinfunction "P2.7_9") (pintype "bidirectional"))
    )
    (net (code "25") (name "/P0_1") (class "Default")
      (node (ref "R11") (pin "1") (pinfunction "1_1") (pintype "passive"))
      (node (ref "U1") (pin "40") (pinfunction "P0.1/CAN1TX_40") (pintype "bidirectional"))
    )
    (net (code "26") (name "/P0_4") (class "Default")
      (node (ref "C8") (pin "1") (pinfunction "1_1") (pintype "passive"))
      (node (ref "CRYSTAL") (pin "2") (pinfunction "2_2") (pintype "passive"))
      (node (ref "U1") (pin "43") (pinfunction "P0.4_43") (pintype "bidirectional"))
    )
    (net (code "27") (name "/P0_5") (class "Default")
      (node (ref "C9") (pin "1") (pinfunction "1_1") (pintype "passive"))
      (node (ref "CRYSTAL") (pin "1") (pinfunction "1_1") (pintype "passive"))
      (node (ref "U1") (pin "44") (pinfunction "P0.5_44") (pintype "bidirectional"))
    )
    (net (code "28") (name "/SAR_BY") (class "Default")
      (node (ref "C6") (pin "1") (pinfunction "1_1") (pintype "passive"))
      (node (ref "U1") (pin "1") (pinfunction "P1.7/VREF_1") (pintype "bidirectional"))
    )
    (net (code "29") (name "/SCL_S1") (class "Default")
      (node (ref "R8") (pin "2") (pinfunction "2_2") (pintype "passive"))
      (node (ref "U1") (pin "2") (pinfunction "P2.0/SCB1:SCL1_2") (pintype "bidirectional"))
      (node (ref "U2") (pin "5") (pinfunction "SCL_5") (pintype "input"))
    )
    (net (code "30") (name "/SCL_S2") (class "Default")
      (node (ref "SCL_S2_C2") (pin "TP") (pinfunction "TP_TP") (pintype "input"))
      (node (ref "U1") (pin "51") (pinfunction "P5.0_51") (pintype "bidirectional"))
    )
    (net (code "31") (name "/SCL_S2_U") (class "Default")
      (node (ref "R10") (pin "2") (pinfunction "2_2") (pintype "passive"))
      (node (ref "SCL_S2_C2_C1") (pin "TP") (pinfunction "TP_TP") (pintype "input"))
      (node (ref "U3") (pin "5") (pinfunction "SCL_5") (pintype "input"))
    )
    (net (code "32") (name "/SCL_S3") (class "Default")
      (node (ref "SCL_S3_C3") (pin "TP") (pinfunction "TP_TP") (pintype "input"))
      (node (ref "U1") (pin "12") (pinfunction "P6.0/CAN0TX_EN_12") (pintype "bidirectional"))
    )
    (net (code "33") (name "/SCL_S3_U") (class "Default")
      (node (ref "R27") (pin "1") (pinfunction "1_1") (pintype "passive"))
      (node (ref "SCL_S3_C3_C2") (pin "TP") (pinfunction "TP_TP") (pintype "input"))
      (node (ref "U4") (pin "5") (pinfunction "SCL_5") (pintype "input"))
    )
    (net (code "34") (name "/SCL_S4") (class "Default")
      (node (ref "SCL_S4_C4") (pin "TP") (pinfunction "TP_TP") (pintype "input"))
      (node (ref "U1") (pin "58") (pinfunction "P1.0_58") (pintype "bidirectional"))
    )
    (net (code "35") (name "/SCL_S4_U") (class "Default")
      (node (ref "SCL_S4_C4_C2") (pin "TP") (pinfunction "TP_TP") (pintype "input"))
      (node (ref "X1") (pin "7") (pinfunction "1_7") (pintype "passive"))
    )
    (net (code "36") (name "/SCL_S4_U_1") (class "Default")
      (node (ref "R25") (pin "1") (pinfunction "1_1") (pintype "passive"))
      (node (ref "U5") (pin "5") (pinfunction "SCL_5") (pintype "input"))
      (node (ref "X2") (pin "7") (pinfunction "1_7") (pintype "passive"))
    )
    (net (code "37") (name "/SDA_S1") (class "Default")
      (node (ref "R6") (pin "2") (pinfunction "2_2") (pintype "passive"))
      (node (ref "U1") (pin "3") (pinfunction "P2.1/SCB1:SDA1_3") (pintype "bidirectional"))
      (node (ref "U2") (pin "4") (pinfunction "SDA_4") (pintype "bidirectional"))
    )
    (net (code "38") (name "/SDA_S2") (class "Default")
      (node (ref "SDA_S2_C1") (pin "TP") (pinfunction "TP_TP") (pintype "input"))
      (node (ref "U1") (pin "52") (pinfunction "P5.1_52") (pintype "bidirectional"))
    )
    (net (code "39") (name "/SDA_S2_U") (class "Default")
      (node (ref "R12") (pin "2") (pinfunction "2_2") (pintype "passive"))
      (node (ref "SDA_S2_C2_C2") (pin "TP") (pinfunction "TP_TP") (pintype "input"))
      (node (ref "U3") (pin "4") (pinfunction "SDA_4") (pintype "bidirectional"))
    )
    (net (code "40") (name "/SDA_S3") (class "Default")
      (node (ref "SDA_S3_C1") (pin "TP") (pinfunction "TP_TP") (pintype "input"))
      (node (ref "U1") (pin "13") (pinfunction "P6.1/CAN0RX_13") (pintype "bidirectional"))
    )
    (net (code "41") (name "/SDA_S3_U") (class "Default")
      (node (ref "R26") (pin "1") (pinfunction "1_1") (pintype "passive"))
      (node (ref "SDA_S3_C3_C4") (pin "TP") (pinfunction "TP_TP") (pintype "input"))
      (node (ref "U4") (pin "4") (pinfunction "SDA_4") (pintype "bidirectional"))
    )
    (net (code "42") (name "/SDA_S4") (class "Default")
      (node (ref "SDA_S4_C1") (pin "TP") (pinfunction "TP_TP") (pintype "input"))
      (node (ref "U1") (pin "59") (pinfunction "P1.1_59") (pintype "bidirectional"))
    )
    (net (code "43") (name "/SDA_S4_U") (class "Default")
      (node (ref "SDA_S4_C4_C4") (pin "TP") (pinfunction "TP_TP") (pintype "input"))
      (node (ref "X1") (pin "8") (pinfunction "1_8") (pintype "passive"))
    )
    (net (code "44") (name "/SDA_S4_U_1") (class "Default")
      (node (ref "R24") (pin "1") (pinfunction "1_1") (pintype "passive"))
      (node (ref "U5") (pin "4") (pinfunction "SDA_4") (pintype "bidirectional"))
      (node (ref "X2") (pin "8") (pinfunction "1_8") (pintype "passive"))
    )
    (net (code "45") (name "/SWDCLK") (class "Default")
      (node (ref "R2") (pin "2") (pinfunction "2_2") (pintype "passive"))
      (node (ref "U1") (pin "21") (pinfunction "P3.3_21") (pintype "bidirectional"))
    )
    (net (code "46") (name "/SWDIO") (class "Default")
      (node (ref "R3") (pin "2") (pinfunction "2_2") (pintype "passive"))
      (node (ref "U1") (pin "20") (pinfunction "P3.2_20") (pintype "bidirectional"))
    )
    (net (code "47") (name "/UART_RX") (class "Default")
      (node (ref "U1") (pin "37") (pinfunction "P7.0/SCB3:SCL1_37") (pintype "bidirectional"))
    )
    (net (code "48") (name "/UART_TX") (class "Default")
      (node (ref "U1") (pin "38") (pinfunction "P7.1/SCB3:SDA1_38") (pintype "bidirectional"))
    )
    (net (code "49") (name "/VCCC") (class "Default")
      (node (ref "DINA") (pin "2") (pinfunction "2_2") (pintype "passive"))
      (node (ref "VCC_1_C1") (pin "TP") (pinfunction "TP_TP") (pintype "input"))
      (node (ref "VCC_2_C1") (pin "TP") (pinfunction "TP_TP") (pintype "input"))
      (node (ref "VCC_3_C1") (pin "TP") (pinfunction "TP_TP") (pintype "input"))
      (node (ref "VCC_4_C1") (pin "TP") (pinfunction "TP_TP") (pintype "input"))
      (node (ref "VCC_C1") (pin "TP") (pinfunction "TP_TP") (pintype "input"))
    )
    (net (code "50") (name "/VCCD") (class "Default")
      (node (ref "C7") (pin "1") (pinfunction "1_1") (pintype "passive"))
      (node (ref "U1") (pin "48") (pinfunction "VCCD_48") (pintype "bidirectional"))
    )
    (net (code "51") (name "/VCC_C2") (class "Default")
      (node (ref "IC1") (pin "3") (pinfunction "IN_3") (pintype "input"))
      (node (ref "VCC_1_C2") (pin "TP") (pinfunction "TP_TP") (pintype "input"))
      (node (ref "VCC_2_C2") (pin "TP") (pinfunction "TP_TP") (pintype "input"))
      (node (ref "VCC_3_C2") (pin "TP") (pinfunction "TP_TP") (pintype "input"))
      (node (ref "VCC_4_C2") (pin "TP") (pinfunction "TP_TP") (pintype "input"))
      (node (ref "VCC_C2") (pin "TP") (pinfunction "TP_TP") (pintype "input"))
      (node (ref "VCC_C2_C3") (pin "TP") (pinfunction "TP_TP") (pintype "input"))
    )
    (net (code "52") (name "/VCC_C3") (class "Default")
      (node (ref "VCC_1_C3") (pin "TP") (pinfunction "TP_TP") (pintype "input"))
      (node (ref "VCC_2_C3") (pin "TP") (pinfunction "TP_TP") (pintype "input"))
      (node (ref "VCC_3_C3") (pin "TP") (pinfunction "TP_TP") (pintype "input"))
      (node (ref "VCC_4_C3") (pin "TP") (pinfunction "TP_TP") (pintype "input"))
      (node (ref "VCC_C3") (pin "TP") (pinfunction "TP_TP") (pintype "input"))
      (node (ref "X1") (pin "1") (pinfunction "1_1") (pintype "passive"))
    )
    (net (code "53") (name "/VCC_C4") (class "Default")
      (node (ref "VCC_1_C4") (pin "TP") (pinfunction "TP_TP") (pintype "input"))
      (node (ref "VCC_2_C4") (pin "TP") (pinfunction "TP_TP") (pintype "input"))
      (node (ref "VCC_3_C4") (pin "TP") (pinfunction "TP_TP") (pintype "input"))
      (node (ref "VCC_4_C4") (pin "TP") (pinfunction "TP_TP") (pintype "input"))
      (node (ref "VCC_REINFORCEMENT") (pin "TP") (pinfunction "TP_TP") (pintype "input"))
      (node (ref "X2") (pin "1") (pinfunction "1_1") (pintype "passive"))
    )
    (net (code "54") (name "/VDDA") (class "Default")
      (node (ref "U1") (pin "11") (pinfunction "VDDA1_11") (pintype "bidirectional"))
      (node (ref "U1") (pin "56") (pinfunction "VDDA2_56") (pintype "bidirectional"))
      (node (ref "VDDA_C1") (pin "TP") (pinfunction "TP_TP") (pintype "input"))
    )
    (net (code "55") (name "/VDDA2") (class "Default")
      (node (ref "L1") (pin "2") (pinfunction "2_2") (pintype "passive"))
      (node (ref "VDDA_C2") (pin "TP") (pinfunction "TP_TP") (pintype "input"))
    )
    (net (code "56") (name "/VDDD") (class "Default")
      (node (ref "U1") (pin "50") (pinfunction "VDDD_50") (pintype "bidirectional"))
      (node (ref "VDDD_C1") (pin "TP") (pinfunction "TP_TP") (pintype "input"))
    )
    (net (code "57") (name "/VDDD2") (class "Default")
      (node (ref "L2") (pin "2") (pinfunction "2_2") (pintype "passive"))
      (node (ref "VDDD_C2") (pin "TP") (pinfunction "TP_TP") (pintype "input"))
    )
    (net (code "58") (name "/VDDIO") (class "Default")
      (node (ref "U1") (pin "26") (pinfunction "VDDIO_26") (pintype "bidirectional"))
      (node (ref "VDDIO_C1") (pin "TP") (pinfunction "TP_TP") (pintype "input"))
    )
    (net (code "59") (name "/VDDIO2") (class "Default")
      (node (ref "R15") (pin "2") (pinfunction "2_2") (pintype "passive"))
      (node (ref "VDDIO_C2") (pin "TP") (pinfunction "TP_TP") (pintype "input"))
    )
    (net (code "60") (name "/XRES") (class "Default")
      (node (ref "C10") (pin "1") (pinfunction "1_1") (pintype "passive"))
      (node (ref "R1") (pin "2") (pinfunction "2_2") (pintype "passive"))
      (node (ref "R14") (pin "2") (pinfunction "2_2") (pintype "passive"))
      (node (ref "U1") (pin "47") (pinfunction "XRES_47") (pintype "bidirectional"))
    )
    (net (code "61") (name "GND1") (class "Default")
      (node (ref "C10") (pin "2") (pinfunction "2_2") (pintype "passive"))
      (node (ref "C4") (pin "2") (pinfunction "2_2") (pintype "passive"))
      (node (ref "C5") (pin "2") (pinfunction "2_2") (pintype "passive"))
      (node (ref "C6") (pin "2") (pinfunction "2_2") (pintype "passive"))
      (node (ref "C7") (pin "2") (pinfunction "2_2") (pintype "passive"))
      (node (ref "C8") (pin "2") (pinfunction "2_2") (pintype "passive"))
      (node (ref "C9") (pin "2") (pinfunction "2_2") (pintype "passive"))
      (node (ref "CN1") (pin "D-") (pinfunction "D-_D-") (pintype "bidirectional"))
      (node (ref "DINA") (pin "3") (pinfunction "3_3") (pintype "passive"))
      (node (ref "GND_1_C1") (pin "TP") (pinfunction "TP_TP") (pintype "input"))
      (node (ref "GND_2_C1") (pin "TP") (pinfunction "TP_TP") (pintype "input"))
      (node (ref "GND_3_C1") (pin "TP") (pinfunction "TP_TP") (pintype "input"))
      (node (ref "GND_4_C1") (pin "TP") (pinfunction "TP_TP") (pintype "input"))
      (node (ref "GND_C1") (pin "TP") (pinfunction "TP_TP") (pintype "input"))
      (node (ref "R13") (pin "1") (pinfunction "1_1") (pintype "passive"))
      (node (ref "R17") (pin "2") (pinfunction "2_2") (pintype "passive"))
      (node (ref "R18") (pin "1") (pinfunction "1_1") (pintype "passive"))
      (node (ref "R19") (pin "2") (pinfunction "2_2") (pintype "passive"))
      (node (ref "R4") (pin "2") (pinfunction "2_2") (pintype "passive"))
      (node (ref "U$1") (pin "2") (pinfunction "GND_2") (pintype "power_in"))
      (node (ref "U1") (pin "10") (pinfunction "VSSA1_10") (pintype "bidirectional"))
      (node (ref "U1") (pin "17") (pinfunction "VSSIO_17") (pintype "bidirectional"))
      (node (ref "U1") (pin "49") (pinfunction "VSSD_49") (pintype "bidirectional"))
      (node (ref "U1") (pin "57") (pinfunction "VSSA2_57") (pintype "bidirectional"))
      (node (ref "U2") (pin "12") (pinfunction "GND_12") (pintype "power_in"))
      (node (ref "U2") (pin "13") (pinfunction "GND_13") (pintype "power_in"))
    )
    (net (code "62") (name "GND2") (class "Default")
      (node (ref "GND_1_C2") (pin "TP") (pinfunction "TP_TP") (pintype "input"))
      (node (ref "GND_2_C2") (pin "TP") (pinfunction "TP_TP") (pintype "input"))
      (node (ref "GND_3_C2") (pin "TP") (pinfunction "TP_TP") (pintype "input"))
      (node (ref "GND_4_C2") (pin "TP") (pinfunction "TP_TP") (pintype "input"))
      (node (ref "GND_C2") (pin "TP") (pinfunction "TP_TP") (pintype "input"))
      (node (ref "GND_C2_C3") (pin "TP") (pinfunction "TP_TP") (pintype "input"))
      (node (ref "IC1") (pin "1") (pinfunction "ADJ_1") (pintype "input"))
      (node (ref "R20") (pin "2") (pinfunction "2_2") (pintype "passive"))
      (node (ref "R23") (pin "2") (pinfunction "2_2") (pintype "passive"))
      (node (ref "R5") (pin "1") (pinfunction "1_1") (pintype "passive"))
      (node (ref "U3") (pin "12") (pinfunction "GND_12") (pintype "power_in"))
      (node (ref "U3") (pin "13") (pinfunction "GND_13") (pintype "power_in"))
    )
    (net (code "63") (name "GND3") (class "Default")
      (node (ref "GND_1_C3") (pin "TP") (pinfunction "TP_TP") (pintype "input"))
      (node (ref "GND_2_C3") (pin "TP") (pinfunction "TP_TP") (pintype "input"))
      (node (ref "GND_3_C3") (pin "TP") (pinfunction "TP_TP") (pintype "input"))
      (node (ref "GND_4_C3") (pin "TP") (pinfunction "TP_TP") (pintype "input"))
      (node (ref "GND_C3") (pin "TP") (pinfunction "TP_TP") (pintype "input"))
      (node (ref "R21") (pin "2") (pinfunction "2_2") (pintype "passive"))
      (node (ref "R7") (pin "1") (pinfunction "1_1") (pintype "passive"))
      (node (ref "U4") (pin "12") (pinfunction "GND_12") (pintype "power_in"))
      (node (ref "U4") (pin "13") (pinfunction "GND_13") (pintype "power_in"))
      (node (ref "X1") (pin "2") (pinfunction "1_2") (pintype "passive"))
      (node (ref "X1") (pin "6") (pinfunction "1_6") (pintype "passive"))
    )
    (net (code "64") (name "GND4") (class "Default")
      (node (ref "GND_1_C4") (pin "TP") (pinfunction "TP_TP") (pintype "input"))
      (node (ref "GND_2_C4") (pin "TP") (pinfunction "TP_TP") (pintype "input"))
      (node (ref "GND_3_C4") (pin "TP") (pinfunction "TP_TP") (pintype "input"))
      (node (ref "GND_4_C4") (pin "TP") (pinfunction "TP_TP") (pintype "input"))
      (node (ref "GND_REINFORCEMENT") (pin "TP") (pinfunction "TP_TP") (pintype "input"))
      (node (ref "R22") (pin "2") (pinfunction "2_2") (pintype "passive"))
      (node (ref "R9") (pin "1") (pinfunction "1_1") (pintype "passive"))
      (node (ref "U5") (pin "12") (pinfunction "GND_12") (pintype "power_in"))
      (node (ref "U5") (pin "13") (pinfunction "GND_13") (pintype "power_in"))
      (node (ref "X2") (pin "2") (pinfunction "1_2") (pintype "passive"))
      (node (ref "X2") (pin "6") (pinfunction "1_6") (pintype "passive"))
    )
    (net (code "65") (name "Net-(CANH_1_C2-PadTP)") (class "Default")
      (node (ref "CANH_1_C2") (pin "TP") (pinfunction "TP_TP") (pintype "input"))
      (node (ref "CANH_2_C2") (pin "TP") (pinfunction "TP_TP") (pintype "input"))
      (node (ref "CANH_3_C2") (pin "TP") (pinfunction "TP_TP") (pintype "input"))
      (node (ref "CANH_4_C2") (pin "TP") (pinfunction "TP_TP") (pintype "input"))
      (node (ref "CANH_C2") (pin "TP") (pinfunction "TP_TP") (pintype "input"))
      (node (ref "CANH_C2_C3") (pin "TP") (pinfunction "TP_TP") (pintype "input"))
    )
    (net (code "66") (name "Net-(CANL_1_C2-PadTP)") (class "Default")
      (node (ref "CANL_1_C2") (pin "TP") (pinfunction "TP_TP") (pintype "input"))
      (node (ref "CANL_2_C2") (pin "TP") (pinfunction "TP_TP") (pintype "input"))
      (node (ref "CANL_3_C2") (pin "TP") (pinfunction "TP_TP") (pintype "input"))
      (node (ref "CANL_4_C2") (pin "TP") (pinfunction "TP_TP") (pintype "input"))
      (node (ref "CANL_C2") (pin "TP") (pinfunction "TP_TP") (pintype "input"))
      (node (ref "CANL_C2_C3") (pin "TP") (pinfunction "TP_TP") (pintype "input"))
    )
    (net (code "67") (name "Net-(CN1-PadD+)") (class "Default")
      (node (ref "CN1") (pin "D+") (pinfunction "D+_D+") (pintype "bidirectional"))
      (node (ref "R1") (pin "1") (pinfunction "1_1") (pintype "passive"))
    )
    (net (code "68") (name "Net-(CN1-PadGND)") (class "Default")
      (node (ref "CN1") (pin "GND") (pinfunction "GND_GND") (pintype "power_in"))
      (node (ref "R3") (pin "1") (pinfunction "1_1") (pintype "passive"))
    )
    (net (code "69") (name "Net-(CN1-PadID)") (class "Default")
      (node (ref "CN1") (pin "ID") (pinfunction "ID_ID") (pintype "bidirectional"))
      (node (ref "R2") (pin "1") (pinfunction "1_1") (pintype "passive"))
    )
    (net (code "70") (name "Net-(LED1-PadC)") (class "Default")
      (node (ref "LED1") (pin "C") (pinfunction "C_C") (pintype "passive"))
      (node (ref "R19") (pin "1") (pinfunction "1_1") (pintype "passive"))
    )
    (net (code "71") (name "Net-(LED2-PadC)") (class "Default")
      (node (ref "LED2") (pin "C") (pinfunction "C_C") (pintype "passive"))
      (node (ref "R20") (pin "1") (pinfunction "1_1") (pintype "passive"))
    )
    (net (code "72") (name "Net-(LED3-PadC)") (class "Default")
      (node (ref "LED3") (pin "C") (pinfunction "C_C") (pintype "passive"))
      (node (ref "R21") (pin "1") (pinfunction "1_1") (pintype "passive"))
    )
    (net (code "73") (name "Net-(LED4-PadC)") (class "Default")
      (node (ref "LED4") (pin "C") (pinfunction "C_C") (pintype "passive"))
      (node (ref "R22") (pin "1") (pinfunction "1_1") (pintype "passive"))
    )
    (net (code "74") (name "Net-(LED5-PadC)") (class "Default")
      (node (ref "LED5") (pin "C") (pinfunction "C_C") (pintype "passive"))
      (node (ref "R23") (pin "1") (pinfunction "1_1") (pintype "passive"))
    )
    (net (code "75") (name "Net-(L_C1_C3-PadTP)") (class "Default")
      (node (ref "L_C1_C3") (pin "TP") (pinfunction "TP_TP") (pintype "input"))
      (node (ref "L_C3_C2") (pin "TP") (pinfunction "TP_TP") (pintype "input"))
    )
    (net (code "76") (name "Net-(L_C1_C4-PadTP)") (class "Default")
      (node (ref "L_C1_C4") (pin "TP") (pinfunction "TP_TP") (pintype "input"))
      (node (ref "L_C4_C1") (pin "TP") (pinfunction "TP_TP") (pintype "input"))
    )
    (net (code "77") (name "Net-(R4-Pad1)") (class "Default")
      (node (ref "R4") (pin "1") (pinfunction "1_1") (pintype "passive"))
      (node (ref "U2") (pin "2") (pinfunction "IR_CA_2") (pintype "power_in"))
      (node (ref "U2") (pin "3") (pinfunction "IR_CA_3") (pintype "power_in"))
    )
    (net (code "78") (name "Net-(R5-Pad2)") (class "Default")
      (node (ref "R5") (pin "2") (pinfunction "2_2") (pintype "passive"))
      (node (ref "U3") (pin "2") (pinfunction "IR_CA_2") (pintype "power_in"))
      (node (ref "U3") (pin "3") (pinfunction "IR_CA_3") (pintype "power_in"))
    )
    (net (code "79") (name "Net-(R7-Pad2)") (class "Default")
      (node (ref "R7") (pin "2") (pinfunction "2_2") (pintype "passive"))
      (node (ref "U4") (pin "2") (pinfunction "IR_CA_2") (pintype "power_in"))
      (node (ref "U4") (pin "3") (pinfunction "IR_CA_3") (pintype "power_in"))
    )
    (net (code "80") (name "Net-(R9-Pad2)") (class "Default")
      (node (ref "R9") (pin "2") (pinfunction "2_2") (pintype "passive"))
      (node (ref "U5") (pin "2") (pinfunction "IR_CA_2") (pintype "power_in"))
      (node (ref "U5") (pin "3") (pinfunction "IR_CA_3") (pintype "power_in"))
    )
    (net (code "81") (name "Net-(R11-Pad2)") (class "Default")
      (node (ref "R11") (pin "2") (pinfunction "2_2") (pintype "passive"))
      (node (ref "R13") (pin "2") (pinfunction "2_2") (pintype "passive"))
    )
    (net (code "82") (name "Net-(SCL_S3_C1_C3-PadTP)") (class "Default")
      (node (ref "SCL_S3_C1_C3") (pin "TP") (pinfunction "TP_TP") (pintype "input"))
      (node (ref "SCL_S3_C3_C1") (pin "TP") (pinfunction "TP_TP") (pintype "input"))
    )
    (net (code "83") (name "Net-(SCL_S4_C1_C4-PadTP)") (class "Default")
      (node (ref "SCL_S4_C1_C4") (pin "TP") (pinfunction "TP_TP") (pintype "input"))
      (node (ref "SCL_S4_C4_C1") (pin "TP") (pinfunction "TP_TP") (pintype "input"))
    )
    (net (code "84") (name "Net-(SDA_S3_C1_C1-PadTP)") (class "Default")
      (node (ref "SDA_S3_C1_C1") (pin "TP") (pinfunction "TP_TP") (pintype "input"))
      (node (ref "SDA_S3_C3_C3") (pin "TP") (pinfunction "TP_TP") (pintype "input"))
    )
    (net (code "85") (name "Net-(SDA_S4_C1_C1-PadTP)") (class "Default")
      (node (ref "SDA_S4_C1_C1") (pin "TP") (pinfunction "TP_TP") (pintype "input"))
      (node (ref "SDA_S4_C4_C3") (pin "TP") (pinfunction "TP_TP") (pintype "input"))
    )
    (net (code "86") (name "Net-(U$1-CANH)") (class "Default")
      (node (ref "R16") (pin "2") (pinfunction "2_2") (pintype "passive"))
      (node (ref "S1") (pin "4") (pinfunction "4_4") (pintype "passive"))
      (node (ref "U$1") (pin "7") (pinfunction "CANH_7") (pintype "bidirectional"))
    )
    (net (code "87") (name "Net-(U$1-RS)") (class "Default")
      (node (ref "R17") (pin "1") (pinfunction "1_1") (pintype "passive"))
      (node (ref "U$1") (pin "8") (pinfunction "RS_8") (pintype "bidirectional"))
    )
    (net (code "88") (name "unconnected-(MECH_LINK_1-PadTP)") (class "Default")
      (node (ref "MECH_LINK_1") (pin "TP") (pinfunction "TP_TP") (pintype "input"))
    )
    (net (code "89") (name "unconnected-(MECH_LINK_2-PadTP)") (class "Default")
      (node (ref "MECH_LINK_2") (pin "TP") (pinfunction "TP_TP") (pintype "input"))
    )
    (net (code "90") (name "unconnected-(MECH_LINK_3-PadTP)") (class "Default")
      (node (ref "MECH_LINK_3") (pin "TP") (pinfunction "TP_TP") (pintype "input"))
    )
    (net (code "91") (name "unconnected-(MECH_LINK_4-PadTP)") (class "Default")
      (node (ref "MECH_LINK_4") (pin "TP") (pinfunction "TP_TP") (pintype "input"))
    )
    (net (code "92") (name "unconnected-(MECH_LINK_5-PadTP)") (class "Default")
      (node (ref "MECH_LINK_5") (pin "TP") (pinfunction "TP_TP") (pintype "input"))
    )
    (net (code "93") (name "unconnected-(MECH_LINK_6-PadTP)") (class "Default")
      (node (ref "MECH_LINK_6") (pin "TP") (pinfunction "TP_TP") (pintype "input"))
    )
    (net (code "94") (name "unconnected-(MECH_LINK_7-PadTP)") (class "Default")
      (node (ref "MECH_LINK_7") (pin "TP") (pinfunction "TP_TP") (pintype "input"))
    )
    (net (code "95") (name "unconnected-(MECH_LINK_8-PadTP)") (class "Default")
      (node (ref "MECH_LINK_8") (pin "TP") (pinfunction "TP_TP") (pintype "input"))
    )
    (net (code "96") (name "unconnected-(MECH_LINK_9-PadTP)") (class "Default")
      (node (ref "MECH_LINK_9") (pin "TP") (pinfunction "TP_TP") (pintype "input"))
    )
    (net (code "97") (name "unconnected-(MECH_LINK_11-PadTP)") (class "Default")
      (node (ref "MECH_LINK_11") (pin "TP") (pinfunction "TP_TP") (pintype "input"))
    )
    (net (code "98") (name "unconnected-(U$1-VREF-Pad5)") (class "Default")
      (node (ref "U$1") (pin "5") (pinfunction "VREF_5") (pintype "bidirectional"))
    )
    (net (code "99") (name "unconnected-(U1-NC1-Pad34)") (class "Default")
      (node (ref "U1") (pin "34") (pinfunction "NC1_34") (pintype "bidirectional"))
    )
    (net (code "100") (name "unconnected-(U1-NC2-Pad35)") (class "Default")
      (node (ref "U1") (pin "35") (pinfunction "NC2_35") (pintype "bidirectional"))
    )
    (net (code "101") (name "unconnected-(U1-NC3-Pad36)") (class "Default")
      (node (ref "U1") (pin "36") (pinfunction "NC3_36") (pintype "bidirectional"))
    )
    (net (code "102") (name "unconnected-(U1-P0.0{slash}CAN1RX-Pad39)") (class "Default")
      (node (ref "U1") (pin "39") (pinfunction "P0.0/CAN1RX_39") (pintype "bidirectional"))
    )
    (net (code "103") (name "unconnected-(U1-P0.2-Pad41)") (class "Default")
      (node (ref "U1") (pin "41") (pinfunction "P0.2_41") (pintype "bidirectional"))
    )
    (net (code "104") (name "unconnected-(U1-P0.3-Pad42)") (class "Default")
      (node (ref "U1") (pin "42") (pinfunction "P0.3_42") (pintype "bidirectional"))
    )
    (net (code "105") (name "unconnected-(U1-P0.6-Pad45)") (class "Default")
      (node (ref "U1") (pin "45") (pinfunction "P0.6_45") (pintype "bidirectional"))
    )
    (net (code "106") (name "unconnected-(U1-P0.7{slash}CAN1TX_EN-Pad46)") (class "Default")
      (node (ref "U1") (pin "46") (pinfunction "P0.7/CAN1TX_EN_46") (pintype "bidirectional"))
    )
    (net (code "107") (name "unconnected-(U1-P1.2-Pad60)") (class "Default")
      (node (ref "U1") (pin "60") (pinfunction "P1.2_60") (pintype "bidirectional"))
    )
    (net (code "108") (name "unconnected-(U1-P1.3-Pad61)") (class "Default")
      (node (ref "U1") (pin "61") (pinfunction "P1.3_61") (pintype "bidirectional"))
    )
    (net (code "109") (name "unconnected-(U1-P1.4-Pad62)") (class "Default")
      (node (ref "U1") (pin "62") (pinfunction "P1.4_62") (pintype "bidirectional"))
    )
    (net (code "110") (name "unconnected-(U1-P1.5-Pad63)") (class "Default")
      (node (ref "U1") (pin "63") (pinfunction "P1.5_63") (pintype "bidirectional"))
    )
    (net (code "111") (name "unconnected-(U1-P1.6-Pad64)") (class "Default")
      (node (ref "U1") (pin "64") (pinfunction "P1.6_64") (pintype "bidirectional"))
    )
    (net (code "112") (name "unconnected-(U1-P3.0{slash}SCB1:RX-Pad18)") (class "Default")
      (node (ref "U1") (pin "18") (pinfunction "P3.0/SCB1:RX_18") (pintype "bidirectional"))
    )
    (net (code "113") (name "unconnected-(U1-P3.1{slash}SCB1:TX-Pad19)") (class "Default")
      (node (ref "U1") (pin "19") (pinfunction "P3.1/SCB1:TX_19") (pintype "bidirectional"))
    )
    (net (code "114") (name "unconnected-(U1-P3.4-Pad22)") (class "Default")
      (node (ref "U1") (pin "22") (pinfunction "P3.4_22") (pintype "bidirectional"))
    )
    (net (code "115") (name "unconnected-(U1-P3.5-Pad23)") (class "Default")
      (node (ref "U1") (pin "23") (pinfunction "P3.5_23") (pintype "bidirectional"))
    )
    (net (code "116") (name "unconnected-(U1-P3.6-Pad24)") (class "Default")
      (node (ref "U1") (pin "24") (pinfunction "P3.6_24") (pintype "bidirectional"))
    )
    (net (code "117") (name "unconnected-(U1-P3.7-Pad25)") (class "Default")
      (node (ref "U1") (pin "25") (pinfunction "P3.7_25") (pintype "bidirectional"))
    )
    (net (code "118") (name "unconnected-(U1-P4.4-Pad31)") (class "Default")
      (node (ref "U1") (pin "31") (pinfunction "P4.4_31") (pintype "bidirectional"))
    )
    (net (code "119") (name "unconnected-(U1-P4.5-Pad32)") (class "Default")
      (node (ref "U1") (pin "32") (pinfunction "P4.5_32") (pintype "bidirectional"))
    )
    (net (code "120") (name "unconnected-(U1-P4.6-Pad33)") (class "Default")
      (node (ref "U1") (pin "33") (pinfunction "P4.6_33") (pintype "bidirectional"))
    )
    (net (code "121") (name "unconnected-(U1-P5.2-Pad53)") (class "Default")
      (node (ref "U1") (pin "53") (pinfunction "P5.2_53") (pintype "bidirectional"))
    )
    (net (code "122") (name "unconnected-(U1-P5.3-Pad54)") (class "Default")
      (node (ref "U1") (pin "54") (pinfunction "P5.3_54") (pintype "bidirectional"))
    )
    (net (code "123") (name "unconnected-(U1-P5.5-Pad55)") (class "Default")
      (node (ref "U1") (pin "55") (pinfunction "P5.5_55") (pintype "bidirectional"))
    )
    (net (code "124") (name "unconnected-(U1-P6.2{slash}CAN0TX-Pad14)") (class "Default")
      (node (ref "U1") (pin "14") (pinfunction "P6.2/CAN0TX_14") (pintype "bidirectional"))
    )
    (net (code "125") (name "unconnected-(U1-P6.4-Pad15)") (class "Default")
      (node (ref "U1") (pin "15") (pinfunction "P6.4_15") (pintype "bidirectional"))
    )
    (net (code "126") (name "unconnected-(U1-P6.5-Pad16)") (class "Default")
      (node (ref "U1") (pin "16") (pinfunction "P6.5_16") (pintype "bidirectional"))
    )
    (net (code "127") (name "unconnected-(U2-INT-Pad6)") (class "Default")
      (node (ref "U2") (pin "6") (pinfunction "INT_6") (pintype "output"))
    )
    (net (code "128") (name "unconnected-(U3-INT-Pad6)") (class "Default")
      (node (ref "U3") (pin "6") (pinfunction "INT_6") (pintype "output"))
    )
    (net (code "129") (name "unconnected-(U4-INT-Pad6)") (class "Default")
      (node (ref "U4") (pin "6") (pinfunction "INT_6") (pintype "output"))
    )
    (net (code "130") (name "unconnected-(U5-INT-Pad6)") (class "Default")
      (node (ref "U5") (pin "6") (pinfunction "INT_6") (pintype "output"))
    )
    (net (code "131") (name "unconnected-(X1B-1-Pad10)") (class "Default")
      (node (ref "X1") (pin "10") (pinfunction "1_10") (pintype "passive"))
    )
    (net (code "132") (name "unconnected-(X2B-1-Pad10)") (class "Default")
      (node (ref "X2") (pin "10") (pinfunction "1_10") (pintype "passive"))
    )
  )
)
